# gvg-300-bus-3rows-usb-horiz-v1.net
KiCad netlist of a schematic drawn in EAGLE
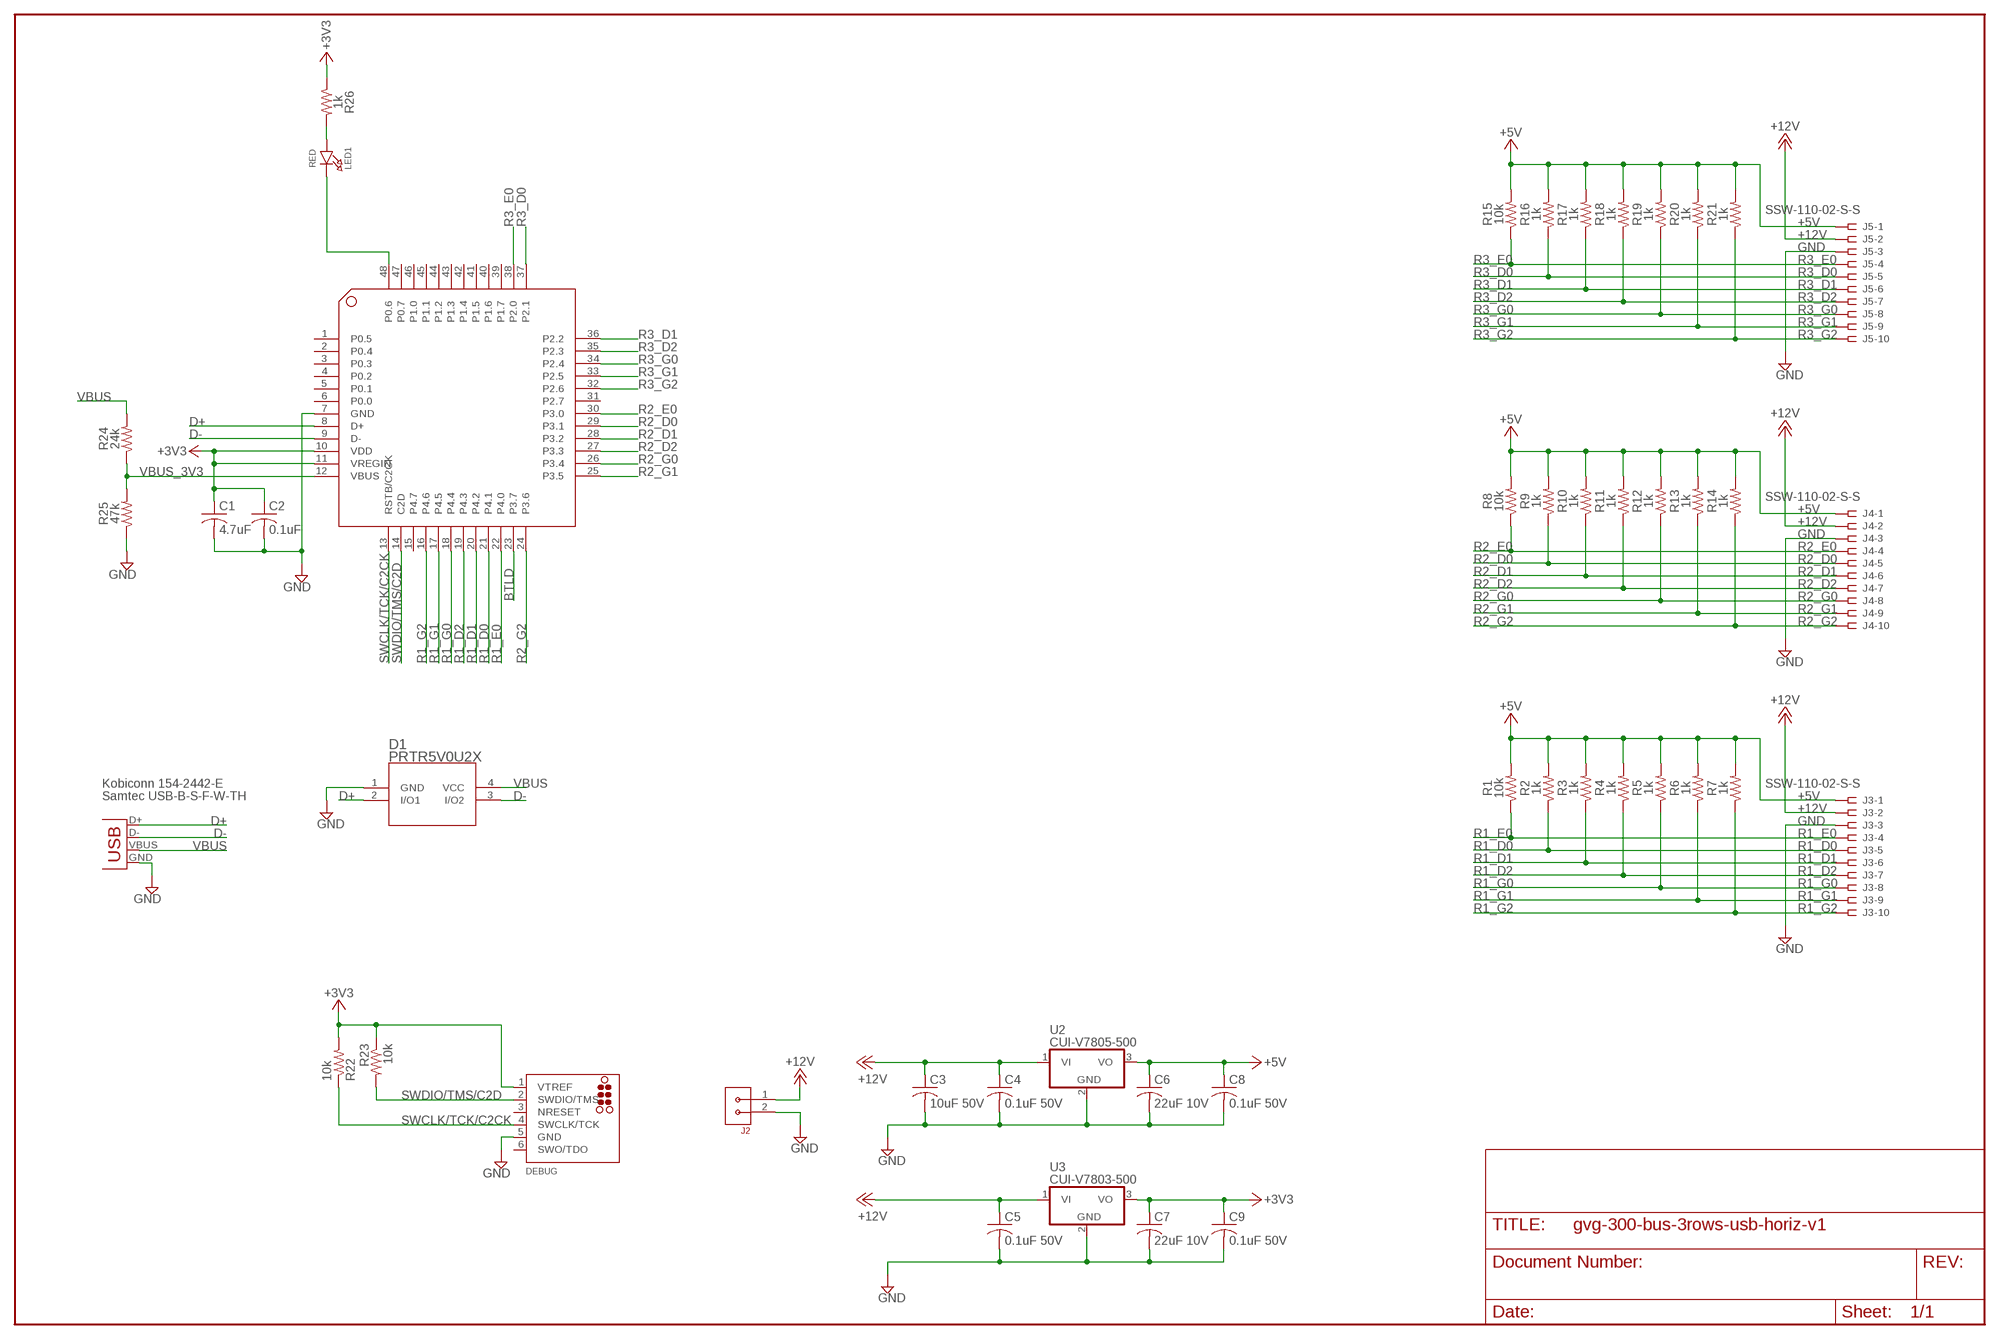
[diagram p0: schematic, sheet 1]

(export (version "E")
  (design (tool "Eeschema 10.0.6"))
  (components
    (comp (ref "C1")
      (value "4.7uF")
      (footprint "eagle-import:C0805K")
      (libsource (lib "eagle-import") (part "C-USC0805K"))
    )
    (comp (ref "C2")
      (value "0.1uF")
      (footprint "eagle-import:C0603K")
      (libsource (lib "eagle-import") (part "C-USC0603K"))
    )
    (comp (ref "C3")
      (value "10uF 50V")
      (footprint "eagle-import:C1210K")
      (fields (field (name "MFR") "KEMET") (field (name "MFR_PART_NO") "C1210C106K5RACTU"))
      (libsource (lib "eagle-import") (part "C-USC1210K"))
    )
    (comp (ref "C4")
      (value "0.1uF 50V")
      (footprint "eagle-import:C1206K")
      (fields (field (name "MFR") "KEMET") (field (name "MFR_PART_NO") "C1206S104M5RACTU"))
      (libsource (lib "eagle-import") (part "C-USC1206K"))
    )
    (comp (ref "C5")
      (value "0.1uF 50V")
      (footprint "eagle-import:C1206K")
      (fields (field (name "MFR") "KEMET") (field (name "MFR_PART_NO") "C1206S104M5RACTU"))
      (libsource (lib "eagle-import") (part "C-USC1206K"))
    )
    (comp (ref "C6")
      (value "22uF 10V")
      (footprint "eagle-import:C1206K")
      (fields (field (name "MFR") "KEMET") (field (name "MFR_PART_NO") "C1206C226K8RAC7800"))
      (libsource (lib "eagle-import") (part "C-USC1206K"))
    )
    (comp (ref "C7")
      (value "22uF 10V")
      (footprint "eagle-import:C1206K")
      (fields (field (name "MFR") "KEMET") (field (name "MFR_PART_NO") "C1206C226K8RAC7800"))
      (libsource (lib "eagle-import") (part "C-USC1206K"))
    )
    (comp (ref "C8")
      (value "0.1uF 50V")
      (footprint "eagle-import:C1206K")
      (fields (field (name "MFR") "KEMET") (field (name "MFR_PART_NO") "C1206S104M5RACTU"))
      (libsource (lib "eagle-import") (part "C-USC1206K"))
    )
    (comp (ref "C9")
      (value "0.1uF 50V")
      (footprint "eagle-import:C1206K")
      (fields (field (name "MFR") "KEMET") (field (name "MFR_PART_NO") "C1206S104M5RACTU"))
      (libsource (lib "eagle-import") (part "C-USC1206K"))
    )
    (comp (ref "D1")
      (value "PRTR5V0U2X")
      (footprint "eagle-import:SOT143B")
      (libsource (lib "eagle-import") (part "PRTR5V0U2X"))
    )
    (comp (ref "DEBUG")
      (value "TC2030-CTX-SWD")
      (footprint "eagle-import:TC2030-MCP-NL")
      (libsource (lib "eagle-import") (part "TC2030-CTX-SWD"))
    )
    (comp (ref "J1")
      (value "USB-B")
      (footprint "eagle-import:USB-B-PTH")
      (fields (field (name "MFR") "KOBICONN") (field (name "MFR_PART_NO") "154-2442-E"))
      (libsource (lib "eagle-import") (part "USBPTH"))
    )
    (comp (ref "J2")
      (value "CON-3.81MM-1X2-PHOENIX")
      (footprint "eagle-import:CON-PHOENIX-3.81-1X2-RA")
      (libsource (lib "eagle-import") (part "CON-3.81MM-1X2-PHOENIX"))
    )
    (comp (ref "J3")
      (value "SSW-110-02-S-S")
      (footprint "eagle-import:SSW-110-02-S-S")
      (libsource (lib "eagle-import") (part "SSW-110-02-S-S"))
    )
    (comp (ref "J4")
      (value "SSW-110-02-S-S")
      (footprint "eagle-import:SSW-110-02-S-S")
      (libsource (lib "eagle-import") (part "SSW-110-02-S-S"))
    )
    (comp (ref "J5")
      (value "SSW-110-02-S-S")
      (footprint "eagle-import:SSW-110-02-S-S")
      (libsource (lib "eagle-import") (part "SSW-110-02-S-S"))
    )
    (comp (ref "LED1")
      (value "RED")
      (footprint "eagle-import:CHIPLED_0805_NOOUTLINE")
      (libsource (lib "eagle-import") (part "LED0805_NOOUTLINE"))
    )
    (comp (ref "R1")
      (value "10k")
      (footprint "eagle-import:R0603")
      (libsource (lib "eagle-import") (part "R-US_R0603"))
    )
    (comp (ref "R2")
      (value "1k")
      (footprint "eagle-import:R0603")
      (libsource (lib "eagle-import") (part "R-US_R0603"))
    )
    (comp (ref "R3")
      (value "1k")
      (footprint "eagle-import:R0603")
      (libsource (lib "eagle-import") (part "R-US_R0603"))
    )
    (comp (ref "R4")
      (value "1k")
      (footprint "eagle-import:R0603")
      (libsource (lib "eagle-import") (part "R-US_R0603"))
    )
    (comp (ref "R5")
      (value "1k")
      (footprint "eagle-import:R0603")
      (libsource (lib "eagle-import") (part "R-US_R0603"))
    )
    (comp (ref "R6")
      (value "1k")
      (footprint "eagle-import:R0603")
      (libsource (lib "eagle-import") (part "R-US_R0603"))
    )
    (comp (ref "R7")
      (value "1k")
      (footprint "eagle-import:R0603")
      (libsource (lib "eagle-import") (part "R-US_R0603"))
    )
    (comp (ref "R8")
      (value "10k")
      (footprint "eagle-import:R0603")
      (libsource (lib "eagle-import") (part "R-US_R0603"))
    )
    (comp (ref "R9")
      (value "1k")
      (footprint "eagle-import:R0603")
      (libsource (lib "eagle-import") (part "R-US_R0603"))
    )
    (comp (ref "R10")
      (value "1k")
      (footprint "eagle-import:R0603")
      (libsource (lib "eagle-import") (part "R-US_R0603"))
    )
    (comp (ref "R11")
      (value "1k")
      (footprint "eagle-import:R0603")
      (libsource (lib "eagle-import") (part "R-US_R0603"))
    )
    (comp (ref "R12")
      (value "1k")
      (footprint "eagle-import:R0603")
      (libsource (lib "eagle-import") (part "R-US_R0603"))
    )
    (comp (ref "R13")
      (value "1k")
      (footprint "eagle-import:R0603")
      (libsource (lib "eagle-import") (part "R-US_R0603"))
    )
    (comp (ref "R14")
      (value "1k")
      (footprint "eagle-import:R0603")
      (libsource (lib "eagle-import") (part "R-US_R0603"))
    )
    (comp (ref "R15")
      (value "10k")
      (footprint "eagle-import:R0603")
      (libsource (lib "eagle-import") (part "R-US_R0603"))
    )
    (comp (ref "R16")
      (value "1k")
      (footprint "eagle-import:R0603")
      (libsource (lib "eagle-import") (part "R-US_R0603"))
    )
    (comp (ref "R17")
      (value "1k")
      (footprint "eagle-import:R0603")
      (libsource (lib "eagle-import") (part "R-US_R0603"))
    )
    (comp (ref "R18")
      (value "1k")
      (footprint "eagle-import:R0603")
      (libsource (lib "eagle-import") (part "R-US_R0603"))
    )
    (comp (ref "R19")
      (value "1k")
      (footprint "eagle-import:R0603")
      (libsource (lib "eagle-import") (part "R-US_R0603"))
    )
    (comp (ref "R20")
      (value "1k")
      (footprint "eagle-import:R0603")
      (libsource (lib "eagle-import") (part "R-US_R0603"))
    )
    (comp (ref "R21")
      (value "1k")
      (footprint "eagle-import:R0603")
      (libsource (lib "eagle-import") (part "R-US_R0603"))
    )
    (comp (ref "R22")
      (value "10k")
      (footprint "eagle-import:R0603")
      (libsource (lib "eagle-import") (part "R-US_R0603"))
    )
    (comp (ref "R23")
      (value "10k")
      (footprint "eagle-import:R0603")
      (libsource (lib "eagle-import") (part "R-US_R0603"))
    )
    (comp (ref "R24")
      (value "24k")
      (footprint "eagle-import:R0603")
      (libsource (lib "eagle-import") (part "R-US_R0603"))
    )
    (comp (ref "R25")
      (value "47k")
      (footprint "eagle-import:R0603")
      (libsource (lib "eagle-import") (part "R-US_R0603"))
    )
    (comp (ref "R26")
      (value "1k")
      (footprint "eagle-import:R0603")
      (libsource (lib "eagle-import") (part "R-US_R0603"))
    )
    (comp (ref "U1")
      (value "EFM8UB20F64G-B-QFP48")
      (footprint "eagle-import:EFM8UB2-QFP48")
      (libsource (lib "eagle-import") (part "EFM8UB20F64G-B-QFP48"))
    )
    (comp (ref "U2")
      (value "CUI-V7805-500")
      (footprint "eagle-import:CUI-78XX-500")
      (libsource (lib "eagle-import") (part "CUI-V7803-500"))
    )
    (comp (ref "U3")
      (value "CUI-V7803-500")
      (footprint "eagle-import:CUI-78XX-500")
      (libsource (lib "eagle-import") (part "CUI-V7803-500"))
    )
  )
  (nets
    (net (code "1") (name "+3V3") (class "Default")
      (node (ref "C1") (pin "1") (pinfunction "1_1") (pintype "passive"))
      (node (ref "C2") (pin "1") (pinfunction "1_1") (pintype "passive"))
      (node (ref "C7") (pin "1") (pinfunction "1_1") (pintype "passive"))
      (node (ref "C9") (pin "1") (pinfunction "1_1") (pintype "passive"))
      (node (ref "DEBUG") (pin "1") (pinfunction "VTREF_1") (pintype "passive"))
      (node (ref "R22") (pin "2") (pinfunction "2_2") (pintype "passive"))
      (node (ref "R23") (pin "1") (pinfunction "1_1") (pintype "passive"))
      (node (ref "R26") (pin "1") (pinfunction "1_1") (pintype "passive"))
      (node (ref "U1") (pin "10") (pinfunction "VDD_10") (pintype "bidirectional"))
      (node (ref "U1") (pin "11") (pinfunction "VREGIN_11") (pintype "bidirectional"))
      (node (ref "U3") (pin "3") (pinfunction "VO_3") (pintype "passive"))
    )
    (net (code "2") (name "+5V") (class "Default")
      (node (ref "C6") (pin "1") (pinfunction "1_1") (pintype "passive"))
      (node (ref "C8") (pin "1") (pinfunction "1_1") (pintype "passive"))
      (node (ref "J3") (pin "1") (pinfunction "1_1") (pintype "passive"))
      (node (ref "J4") (pin "1") (pinfunction "1_1") (pintype "passive"))
      (node (ref "J5") (pin "1") (pinfunction "1_1") (pintype "passive"))
      (node (ref "R1") (pin "2") (pinfunction "2_2") (pintype "passive"))
      (node (ref "R10") (pin "2") (pinfunction "2_2") (pintype "passive"))
      (node (ref "R11") (pin "2") (pinfunction "2_2") (pintype "passive"))
      (node (ref "R12") (pin "2") (pinfunction "2_2") (pintype "passive"))
      (node (ref "R13") (pin "2") (pinfunction "2_2") (pintype "passive"))
      (node (ref "R14") (pin "2") (pinfunction "2_2") (pintype "passive"))
      (node (ref "R15") (pin "2") (pinfunction "2_2") (pintype "passive"))
      (node (ref "R16") (pin "2") (pinfunction "2_2") (pintype "passive"))
      (node (ref "R17") (pin "2") (pinfunction "2_2") (pintype "passive"))
      (node (ref "R18") (pin "2") (pinfunction "2_2") (pintype "passive"))
      (node (ref "R19") (pin "2") (pinfunction "2_2") (pintype "passive"))
      (node (ref "R2") (pin "2") (pinfunction "2_2") (pintype "passive"))
      (node (ref "R20") (pin "2") (pinfunction "2_2") (pintype "passive"))
      (node (ref "R21") (pin "2") (pinfunction "2_2") (pintype "passive"))
      (node (ref "R3") (pin "2") (pinfunction "2_2") (pintype "passive"))
      (node (ref "R4") (pin "2") (pinfunction "2_2") (pintype "passive"))
      (node (ref "R5") (pin "2") (pinfunction "2_2") (pintype "passive"))
      (node (ref "R6") (pin "2") (pinfunction "2_2") (pintype "passive"))
      (node (ref "R7") (pin "2") (pinfunction "2_2") (pintype "passive"))
      (node (ref "R8") (pin "2") (pinfunction "2_2") (pintype "passive"))
      (node (ref "R9") (pin "2") (pinfunction "2_2") (pintype "passive"))
      (node (ref "U2") (pin "3") (pinfunction "VO_3") (pintype "passive"))
    )
    (net (code "3") (name "+12V") (class "Default")
      (node (ref "C3") (pin "1") (pinfunction "1_1") (pintype "passive"))
      (node (ref "C4") (pin "1") (pinfunction "1_1") (pintype "passive"))
      (node (ref "C5") (pin "1") (pinfunction "1_1") (pintype "passive"))
      (node (ref "J2") (pin "1") (pinfunction "1_1") (pintype "bidirectional"))
      (node (ref "J3") (pin "2") (pinfunction "1_2") (pintype "passive"))
      (node (ref "J4") (pin "2") (pinfunction "1_2") (pintype "passive"))
      (node (ref "J5") (pin "2") (pinfunction "1_2") (pintype "passive"))
      (node (ref "U2") (pin "1") (pinfunction "VI_1") (pintype "input"))
      (node (ref "U3") (pin "1") (pinfunction "VI_1") (pintype "input"))
    )
    (net (code "4") (name "/BTLD") (class "Default")
      (node (ref "U1") (pin "23") (pinfunction "P3.7_23") (pintype "bidirectional"))
    )
    (net (code "5") (name "/D+") (class "Default")
      (node (ref "D1") (pin "2") (pinfunction "I/O1_2") (pintype "passive"))
      (node (ref "J1") (pin "D+") (pinfunction "D+_D+") (pintype "bidirectional"))
      (node (ref "U1") (pin "8") (pinfunction "D+_8") (pintype "bidirectional"))
    )
    (net (code "6") (name "/D-") (class "Default")
      (node (ref "D1") (pin "3") (pinfunction "I/O2_3") (pintype "passive"))
      (node (ref "J1") (pin "D-") (pinfunction "D-_D-") (pintype "bidirectional"))
      (node (ref "U1") (pin "9") (pinfunction "D-_9") (pintype "bidirectional"))
    )
    (net (code "7") (name "/NRESET") (class "Default")
      (node (ref "DEBUG") (pin "3") (pinfunction "NRESET_3") (pintype "power_in"))
    )
    (net (code "8") (name "/R1_D0") (class "Default")
      (node (ref "J3") (pin "5") (pinfunction "1_5") (pintype "passive"))
      (node (ref "R2") (pin "1") (pinfunction "1_1") (pintype "passive"))
      (node (ref "U1") (pin "21") (pinfunction "P4.1_21") (pintype "bidirectional"))
    )
    (net (code "9") (name "/R1_D1") (class "Default")
      (node (ref "J3") (pin "6") (pinfunction "1_6") (pintype "passive"))
      (node (ref "R3") (pin "1") (pinfunction "1_1") (pintype "passive"))
      (node (ref "U1") (pin "20") (pinfunction "P4.2_20") (pintype "bidirectional"))
    )
    (net (code "10") (name "/R1_D2") (class "Default")
      (node (ref "J3") (pin "7") (pinfunction "1_7") (pintype "passive"))
      (node (ref "R4") (pin "1") (pinfunction "1_1") (pintype "passive"))
      (node (ref "U1") (pin "19") (pinfunction "P4.3_19") (pintype "bidirectional"))
    )
    (net (code "11") (name "/R1_E0") (class "Default")
      (node (ref "J3") (pin "4") (pinfunction "1_4") (pintype "passive"))
      (node (ref "R1") (pin "1") (pinfunction "1_1") (pintype "passive"))
      (node (ref "U1") (pin "22") (pinfunction "P4.0_22") (pintype "bidirectional"))
    )
    (net (code "12") (name "/R1_G0") (class "Default")
      (node (ref "J3") (pin "8") (pinfunction "1_8") (pintype "passive"))
      (node (ref "R5") (pin "1") (pinfunction "1_1") (pintype "passive"))
      (node (ref "U1") (pin "18") (pinfunction "P4.4_18") (pintype "bidirectional"))
    )
    (net (code "13") (name "/R1_G1") (class "Default")
      (node (ref "J3") (pin "9") (pinfunction "1_9") (pintype "passive"))
      (node (ref "R6") (pin "1") (pinfunction "1_1") (pintype "passive"))
      (node (ref "U1") (pin "17") (pinfunction "P4.5_17") (pintype "bidirectional"))
    )
    (net (code "14") (name "/R1_G2") (class "Default")
      (node (ref "J3") (pin "10") (pinfunction "1_10") (pintype "passive"))
      (node (ref "R7") (pin "1") (pinfunction "1_1") (pintype "passive"))
      (node (ref "U1") (pin "16") (pinfunction "P4.6_16") (pintype "bidirectional"))
    )
    (net (code "15") (name "/R2_D0") (class "Default")
      (node (ref "J4") (pin "5") (pinfunction "1_5") (pintype "passive"))
      (node (ref "R9") (pin "1") (pinfunction "1_1") (pintype "passive"))
      (node (ref "U1") (pin "29") (pinfunction "P3.1_29") (pintype "bidirectional"))
    )
    (net (code "16") (name "/R2_D1") (class "Default")
      (node (ref "J4") (pin "6") (pinfunction "1_6") (pintype "passive"))
      (node (ref "R10") (pin "1") (pinfunction "1_1") (pintype "passive"))
      (node (ref "U1") (pin "28") (pinfunction "P3.2_28") (pintype "bidirectional"))
    )
    (net (code "17") (name "/R2_D2") (class "Default")
      (node (ref "J4") (pin "7") (pinfunction "1_7") (pintype "passive"))
      (node (ref "R11") (pin "1") (pinfunction "1_1") (pintype "passive"))
      (node (ref "U1") (pin "27") (pinfunction "P3.3_27") (pintype "bidirectional"))
    )
    (net (code "18") (name "/R2_E0") (class "Default")
      (node (ref "J4") (pin "4") (pinfunction "1_4") (pintype "passive"))
      (node (ref "R8") (pin "1") (pinfunction "1_1") (pintype "passive"))
      (node (ref "U1") (pin "30") (pinfunction "P3.0_30") (pintype "bidirectional"))
    )
    (net (code "19") (name "/R2_G0") (class "Default")
      (node (ref "J4") (pin "8") (pinfunction "1_8") (pintype "passive"))
      (node (ref "R12") (pin "1") (pinfunction "1_1") (pintype "passive"))
      (node (ref "U1") (pin "26") (pinfunction "P3.4_26") (pintype "bidirectional"))
    )
    (net (code "20") (name "/R2_G1") (class "Default")
      (node (ref "J4") (pin "9") (pinfunction "1_9") (pintype "passive"))
      (node (ref "R13") (pin "1") (pinfunction "1_1") (pintype "passive"))
      (node (ref "U1") (pin "25") (pinfunction "P3.5_25") (pintype "bidirectional"))
    )
    (net (code "21") (name "/R2_G2") (class "Default")
      (node (ref "J4") (pin "10") (pinfunction "1_10") (pintype "passive"))
      (node (ref "R14") (pin "1") (pinfunction "1_1") (pintype "passive"))
      (node (ref "U1") (pin "24") (pinfunction "P3.6_24") (pintype "bidirectional"))
    )
    (net (code "22") (name "/R3_D0") (class "Default")
      (node (ref "J5") (pin "5") (pinfunction "1_5") (pintype "passive"))
      (node (ref "R16") (pin "1") (pinfunction "1_1") (pintype "passive"))
      (node (ref "U1") (pin "37") (pinfunction "P2.1_37") (pintype "bidirectional"))
    )
    (net (code "23") (name "/R3_D1") (class "Default")
      (node (ref "J5") (pin "6") (pinfunction "1_6") (pintype "passive"))
      (node (ref "R17") (pin "1") (pinfunction "1_1") (pintype "passive"))
      (node (ref "U1") (pin "36") (pinfunction "P2.2_36") (pintype "bidirectional"))
    )
    (net (code "24") (name "/R3_D2") (class "Default")
      (node (ref "J5") (pin "7") (pinfunction "1_7") (pintype "passive"))
      (node (ref "R18") (pin "1") (pinfunction "1_1") (pintype "passive"))
      (node (ref "U1") (pin "35") (pinfunction "P2.3_35") (pintype "bidirectional"))
    )
    (net (code "25") (name "/R3_E0") (class "Default")
      (node (ref "J5") (pin "4") (pinfunction "1_4") (pintype "passive"))
      (node (ref "R15") (pin "1") (pinfunction "1_1") (pintype "passive"))
      (node (ref "U1") (pin "38") (pinfunction "P2.0_38") (pintype "bidirectional"))
    )
    (net (code "26") (name "/R3_G0") (class "Default")
      (node (ref "J5") (pin "8") (pinfunction "1_8") (pintype "passive"))
      (node (ref "R19") (pin "1") (pinfunction "1_1") (pintype "passive"))
      (node (ref "U1") (pin "34") (pinfunction "P2.4_34") (pintype "bidirectional"))
    )
    (net (code "27") (name "/R3_G1") (class "Default")
      (node (ref "J5") (pin "9") (pinfunction "1_9") (pintype "passive"))
      (node (ref "R20") (pin "1") (pinfunction "1_1") (pintype "passive"))
      (node (ref "U1") (pin "33") (pinfunction "P2.5_33") (pintype "bidirectional"))
    )
    (net (code "28") (name "/R3_G2") (class "Default")
      (node (ref "J5") (pin "10") (pinfunction "1_10") (pintype "passive"))
      (node (ref "R21") (pin "1") (pinfunction "1_1") (pintype "passive"))
      (node (ref "U1") (pin "32") (pinfunction "P2.6_32") (pintype "bidirectional"))
    )
    (net (code "29") (name "/SWCLK{slash}TCK{slash}C2CK") (class "Default")
      (node (ref "DEBUG") (pin "4") (pinfunction "SWCLK/TCK_4") (pintype "bidirectional"))
      (node (ref "R22") (pin "1") (pinfunction "1_1") (pintype "passive"))
      (node (ref "U1") (pin "13") (pinfunction "RSTB/C2CK_13") (pintype "bidirectional"))
    )
    (net (code "30") (name "/SWDIO{slash}TMS{slash}C2D") (class "Default")
      (node (ref "DEBUG") (pin "2") (pinfunction "SWDIO/TMS_2") (pintype "power_in"))
      (node (ref "R23") (pin "2") (pinfunction "2_2") (pintype "passive"))
      (node (ref "U1") (pin "14") (pinfunction "C2D_14") (pintype "bidirectional"))
    )
    (net (code "31") (name "/VBUS") (class "Default")
      (node (ref "D1") (pin "4") (pinfunction "VCC_4") (pintype "passive"))
      (node (ref "J1") (pin "VBUS") (pinfunction "VBUS_VBUS") (pintype "bidirectional"))
      (node (ref "R24") (pin "2") (pinfunction "2_2") (pintype "passive"))
    )
    (net (code "32") (name "/VBUS_3V3") (class "Default")
      (node (ref "R24") (pin "1") (pinfunction "1_1") (pintype "passive"))
      (node (ref "R25") (pin "2") (pinfunction "2_2") (pintype "passive"))
      (node (ref "U1") (pin "12") (pinfunction "VBUS_12") (pintype "bidirectional"))
    )
    (net (code "33") (name "GND") (class "Default")
      (node (ref "C1") (pin "2") (pinfunction "2_2") (pintype "passive"))
      (node (ref "C2") (pin "2") (pinfunction "2_2") (pintype "passive"))
      (node (ref "C3") (pin "2") (pinfunction "2_2") (pintype "passive"))
      (node (ref "C4") (pin "2") (pinfunction "2_2") (pintype "passive"))
      (node (ref "C5") (pin "2") (pinfunction "2_2") (pintype "passive"))
      (node (ref "C6") (pin "2") (pinfunction "2_2") (pintype "passive"))
      (node (ref "C7") (pin "2") (pinfunction "2_2") (pintype "passive"))
      (node (ref "C8") (pin "2") (pinfunction "2_2") (pintype "passive"))
      (node (ref "C9") (pin "2") (pinfunction "2_2") (pintype "passive"))
      (node (ref "D1") (pin "1") (pinfunction "GND_1") (pintype "passive"))
      (node (ref "DEBUG") (pin "5") (pinfunction "GND_5") (pintype "output"))
      (node (ref "J1") (pin "GND") (pinfunction "GND_GND") (pintype "bidirectional"))
      (node (ref "J2") (pin "2") (pinfunction "2_2") (pintype "bidirectional"))
      (node (ref "J3") (pin "3") (pinfunction "1_3") (pintype "passive"))
      (node (ref "J4") (pin "3") (pinfunction "1_3") (pintype "passive"))
      (node (ref "J5") (pin "3") (pinfunction "1_3") (pintype "passive"))
      (node (ref "R25") (pin "1") (pinfunction "1_1") (pintype "passive"))
      (node (ref "U1") (pin "7") (pinfunction "GND_7") (pintype "bidirectional"))
      (node (ref "U2") (pin "2") (pinfunction "GND_2") (pintype "passive"))
      (node (ref "U3") (pin "2") (pinfunction "GND_2") (pintype "passive"))
    )
    (net (code "34") (name "Net-(LED1-PadA)") (class "Default")
      (node (ref "LED1") (pin "A") (pinfunction "A_A") (pintype "passive"))
      (node (ref "R26") (pin "2") (pinfunction "2_2") (pintype "passive"))
    )
    (net (code "35") (name "Net-(U1-P0.6)") (class "Default")
      (node (ref "LED1") (pin "C") (pinfunction "C_C") (pintype "passive"))
      (node (ref "U1") (pin "48") (pinfunction "P0.6_48") (pintype "bidirectional"))
    )
    (net (code "36") (name "unconnected-(DEBUG-SWO{slash}TDO-Pad6)") (class "Default")
      (node (ref "DEBUG") (pin "6") (pinfunction "SWO/TDO_6") (pintype "bidirectional"))
    )
    (net (code "37") (name "unconnected-(U1-P0.0-Pad6)") (class "Default")
      (node (ref "U1") (pin "6") (pinfunction "P0.0_6") (pintype "bidirectional"))
    )
    (net (code "38") (name "unconnected-(U1-P0.1-Pad5)") (class "Default")
      (node (ref "U1") (pin "5") (pinfunction "P0.1_5") (pintype "bidirectional"))
    )
    (net (code "39") (name "unconnected-(U1-P0.2-Pad4)") (class "Default")
      (node (ref "U1") (pin "4") (pinfunction "P0.2_4") (pintype "bidirectional"))
    )
    (net (code "40") (name "unconnected-(U1-P0.3-Pad3)") (class "Default")
      (node (ref "U1") (pin "3") (pinfunction "P0.3_3") (pintype "bidirectional"))
    )
    (net (code "41") (name "unconnected-(U1-P0.4-Pad2)") (class "Default")
      (node (ref "U1") (pin "2") (pinfunction "P0.4_2") (pintype "bidirectional"))
    )
    (net (code "42") (name "unconnected-(U1-P0.5-Pad1)") (class "Default")
      (node (ref "U1") (pin "1") (pinfunction "P0.5_1") (pintype "bidirectional"))
    )
    (net (code "43") (name "unconnected-(U1-P0.7-Pad47)") (class "Default")
      (node (ref "U1") (pin "47") (pinfunction "P0.7_47") (pintype "bidirectional"))
    )
    (net (code "44") (name "unconnected-(U1-P1.0-Pad46)") (class "Default")
      (node (ref "U1") (pin "46") (pinfunction "P1.0_46") (pintype "bidirectional"))
    )
    (net (code "45") (name "unconnected-(U1-P1.1-Pad45)") (class "Default")
      (node (ref "U1") (pin "45") (pinfunction "P1.1_45") (pintype "bidirectional"))
    )
    (net (code "46") (name "unconnected-(U1-P1.2-Pad44)") (class "Default")
      (node (ref "U1") (pin "44") (pinfunction "P1.2_44") (pintype "bidirectional"))
    )
    (net (code "47") (name "unconnected-(U1-P1.3-Pad43)") (class "Default")
      (node (ref "U1") (pin "43") (pinfunction "P1.3_43") (pintype "bidirectional"))
    )
    (net (code "48") (name "unconnected-(U1-P1.4-Pad42)") (class "Default")
      (node (ref "U1") (pin "42") (pinfunction "P1.4_42") (pintype "bidirectional"))
    )
    (net (code "49") (name "unconnected-(U1-P1.5-Pad41)") (class "Default")
      (node (ref "U1") (pin "41") (pinfunction "P1.5_41") (pintype "bidirectional"))
    )
    (net (code "50") (name "unconnected-(U1-P1.6-Pad40)") (class "Default")
      (node (ref "U1") (pin "40") (pinfunction "P1.6_40") (pintype "bidirectional"))
    )
    (net (code "51") (name "unconnected-(U1-P1.7-Pad39)") (class "Default")
      (node (ref "U1") (pin "39") (pinfunction "P1.7_39") (pintype "bidirectional"))
    )
    (net (code "52") (name "unconnected-(U1-P2.7-Pad31)") (class "Default")
      (node (ref "U1") (pin "31") (pinfunction "P2.7_31") (pintype "bidirectional"))
    )
    (net (code "53") (name "unconnected-(U1-P4.7-Pad15)") (class "Default")
      (node (ref "U1") (pin "15") (pinfunction "P4.7_15") (pintype "bidirectional"))
    )
  )
)
